# Sheet2.net
KiCad netlist of a schematic drawn in Altium Designer
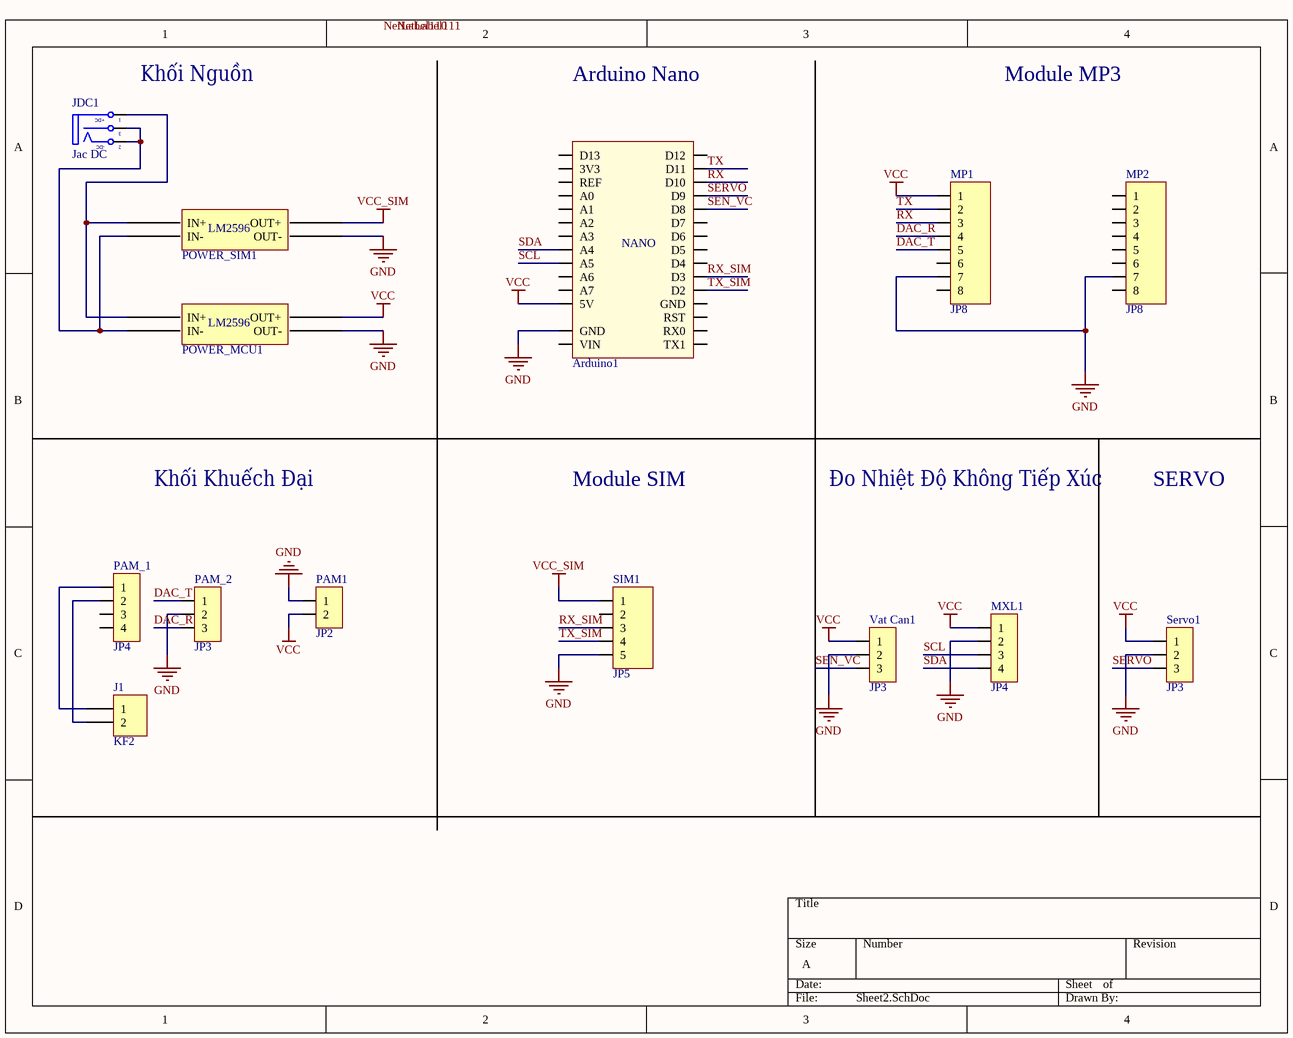
[diagram p0: Sheet2.SchDoc]

(export (version "E")
  (design (tool "Eeschema 10.0.6"))
  (components
    (comp (ref "Arduino1")
      (value "Arduino Nano")
      (footprint "Arduino Nano")
      (description "Arduino NANO")
      (libsource (lib "LIBRARY") (part "Arduino Nano"))
    )
    (comp (ref "J1")
      (value "KF2")
      (footprint "KF2-3.5")
      (fields
        (field (name "MANUFACTURER") "Würth Elektronik eiSos GmbH")
        (field (name "PARTNO") "691103110002")
        (field (name "CREATED BY") "Karrer Zheng")
      )
      (libsource (lib "LIBRARY") (part "KF2"))
    )
    (comp (ref "JDC1")
      (value "Jac DC")
      (footprint "DC0")
      (description "Jac DC input")
      (libsource (lib "LIBRARY") (part "DCIN"))
    )
    (comp (ref "MP1")
      (value "JP8")
      (footprint "JP8-C1C")
      (description "WR-PHD 2.54 mm Angled Socket Header")
      (fields
        (field (name "MANUFACTURER") "Würth Elektronik eiSos GmbH")
        (field (name "PARTNO") "613008143121")
        (field (name "CREATED BY") "Karrer Zheng")
      )
      (libsource (lib "LIBRARY") (part "JP8"))
    )
    (comp (ref "MP2")
      (value "JP8")
      (footprint "JP8-C1C")
      (description "WR-PHD 2.54 mm Angled Socket Header")
      (fields
        (field (name "MANUFACTURER") "Würth Elektronik eiSos GmbH")
        (field (name "PARTNO") "613008143121")
        (field (name "CREATED BY") "Karrer Zheng")
      )
      (libsource (lib "LIBRARY") (part "JP8"))
    )
    (comp (ref "MXL1")
      (value "JP4")
      (footprint "JP4-C1T")
      (description "WR-PHD 2.54 mm Angled Socket Header")
      (fields
        (field (name "MANUFACTURER") "Würth Elektronik eiSos GmbH")
        (field (name "PARTNO") "613004143121")
        (field (name "CREATED BY") "Karrer Zheng")
      )
      (libsource (lib "LIBRARY") (part "JP4"))
    )
    (comp (ref "PAM1")
      (value "JP2")
      (footprint "JP2-C1T")
      (description "WR-PHD 2.54 mm Angled Socket Header")
      (fields
        (field (name "MANUFACTURER") "Würth Elektronik eiSos GmbH")
        (field (name "PARTNO") "613002143121")
        (field (name "CREATED BY") "Karrer Zheng")
      )
      (libsource (lib "LIBRARY") (part "JP2"))
    )
    (comp (ref "PAM_1")
      (value "JP4")
      (footprint "JP4-C1T")
      (description "WR-PHD 2.54 mm Angled Socket Header")
      (fields
        (field (name "MANUFACTURER") "Würth Elektronik eiSos GmbH")
        (field (name "PARTNO") "613004143121")
        (field (name "CREATED BY") "Karrer Zheng")
      )
      (libsource (lib "LIBRARY") (part "JP4"))
    )
    (comp (ref "PAM_2")
      (value "JP3")
      (footprint "JP3-C1T")
      (description "WR-PHD 2.54 mm Angled Socket Header")
      (fields
        (field (name "MANUFACTURER") "Würth Elektronik eiSos GmbH")
        (field (name "PARTNO") "613003143121")
        (field (name "CREATED BY") "Karrer Zheng")
      )
      (libsource (lib "LIBRARY") (part "JP3"))
    )
    (comp (ref "POWER_MCU1")
      (value "BUCK_LM2596")
      (footprint "BUCK_LM2596")
      (libsource (lib "BUCK_LM2596_Sch") (part "BUCK_LM2596"))
    )
    (comp (ref "POWER_SIM1")
      (value "BUCK_LM2596")
      (footprint "BUCK_LM2596")
      (libsource (lib "BUCK_LM2596_Sch") (part "BUCK_LM2596"))
    )
    (comp (ref "Servo1")
      (value "JP3")
      (footprint "JP3-C1T")
      (description "WR-PHD 2.54 mm Angled Socket Header")
      (fields
        (field (name "MANUFACTURER") "Würth Elektronik eiSos GmbH")
        (field (name "PARTNO") "613003143121")
        (field (name "CREATED BY") "Karrer Zheng")
      )
      (libsource (lib "LIBRARY") (part "JP3"))
    )
    (comp (ref "SIM1")
      (value "JP5")
      (footprint "JP5-C1T")
      (description "WR-PHD 2.54 mm Angled Socket Header")
      (fields
        (field (name "MANUFACTURER") "Würth Elektronik eiSos GmbH")
        (field (name "PARTNO") "613005143121")
        (field (name "CREATED BY") "Karrer Zheng")
      )
      (libsource (lib "LIBRARY") (part "JP5"))
    )
    (comp (ref "Vat Can1")
      (value "JP3")
      (footprint "JP3-C1T")
      (description "WR-PHD 2.54 mm Angled Socket Header")
      (fields
        (field (name "MANUFACTURER") "Würth Elektronik eiSos GmbH")
        (field (name "PARTNO") "613003143121")
        (field (name "CREATED BY") "Karrer Zheng")
      )
      (libsource (lib "LIBRARY") (part "JP3"))
    )
  )
  (nets
    (net (code "1") (name "/DAC_R") (class "Default")
      (node (ref "MP1") (pin "4") (pinfunction "4_4") (pintype "passive"))
      (node (ref "PAM_2") (pin "3") (pinfunction "3_3") (pintype "passive"))
    )
    (net (code "2") (name "/DAC_T") (class "Default")
      (node (ref "MP1") (pin "5") (pinfunction "5_5") (pintype "passive"))
      (node (ref "PAM_2") (pin "1") (pinfunction "1_1") (pintype "passive"))
    )
    (net (code "5") (name "/RX") (class "Default")
      (node (ref "Arduino1") (pin "D10") (pinfunction "D10_D10") (pintype "passive"))
      (node (ref "MP1") (pin "3") (pinfunction "3_3") (pintype "passive"))
    )
    (net (code "6") (name "/RX_SIM") (class "Default")
      (node (ref "Arduino1") (pin "D3") (pinfunction "D3_D3") (pintype "passive"))
      (node (ref "SIM1") (pin "3") (pinfunction "3_3") (pintype "passive"))
    )
    (net (code "7") (name "/SCL") (class "Default")
      (node (ref "Arduino1") (pin "A5") (pinfunction "A5_A5") (pintype "passive"))
      (node (ref "MXL1") (pin "3") (pinfunction "3_3") (pintype "passive"))
    )
    (net (code "8") (name "/SDA") (class "Default")
      (node (ref "Arduino1") (pin "A4") (pinfunction "A4_A4") (pintype "passive"))
      (node (ref "MXL1") (pin "4") (pinfunction "4_4") (pintype "passive"))
    )
    (net (code "9") (name "/SEN_VC") (class "Default")
      (node (ref "Arduino1") (pin "D8") (pinfunction "D8_D8") (pintype "passive"))
      (node (ref "Vat Can1") (pin "3") (pinfunction "3_3") (pintype "passive"))
    )
    (net (code "10") (name "/SERVO") (class "Default")
      (node (ref "Arduino1") (pin "D9") (pinfunction "D9_D9") (pintype "passive"))
      (node (ref "Servo1") (pin "3") (pinfunction "3_3") (pintype "passive"))
    )
    (net (code "11") (name "/TX") (class "Default")
      (node (ref "Arduino1") (pin "D11") (pinfunction "D11_D11") (pintype "passive"))
      (node (ref "MP1") (pin "2") (pinfunction "2_2") (pintype "passive"))
    )
    (net (code "12") (name "/TX_SIM") (class "Default")
      (node (ref "Arduino1") (pin "D2") (pinfunction "D2_D2") (pintype "passive"))
      (node (ref "SIM1") (pin "4") (pinfunction "4_4") (pintype "passive"))
    )
    (net (code "13") (name "GND") (class "Default")
      (node (ref "Arduino1") (pin "GND") (pinfunction "GND_GND") (pintype "passive"))
      (node (ref "MP1") (pin "7") (pinfunction "7_7") (pintype "passive"))
      (node (ref "MP2") (pin "7") (pinfunction "7_7") (pintype "passive"))
      (node (ref "MXL1") (pin "2") (pinfunction "2_2") (pintype "passive"))
      (node (ref "PAM1") (pin "1") (pinfunction "1_1") (pintype "passive"))
      (node (ref "PAM_2") (pin "2") (pinfunction "2_2") (pintype "passive"))
      (node (ref "POWER_MCU1") (pin "3") (pinfunction "OUT-_3") (pintype "passive"))
      (node (ref "POWER_SIM1") (pin "3") (pinfunction "OUT-_3") (pintype "passive"))
      (node (ref "SIM1") (pin "5") (pinfunction "5_5") (pintype "passive"))
      (node (ref "Servo1") (pin "2") (pinfunction "2_2") (pintype "passive"))
      (node (ref "Vat Can1") (pin "2") (pinfunction "2_2") (pintype "passive"))
    )
    (net (code "14") (name "Net-(J1-Pad1)") (class "Default")
      (node (ref "J1") (pin "1") (pinfunction "1_1") (pintype "passive"))
      (node (ref "PAM_1") (pin "1") (pinfunction "1_1") (pintype "passive"))
    )
    (net (code "15") (name "Net-(J1-Pad2)") (class "Default")
      (node (ref "J1") (pin "2") (pinfunction "2_2") (pintype "passive"))
      (node (ref "PAM_1") (pin "2") (pinfunction "2_2") (pintype "passive"))
    )
    (net (code "16") (name "Net-(JDC1-S)") (class "Default")
      (node (ref "JDC1") (pin "2") (pinfunction "TN_2") (pintype "passive"))
      (node (ref "JDC1") (pin "3") (pinfunction "S_3") (pintype "power_in"))
      (node (ref "POWER_MCU1") (pin "2") (pinfunction "IN-_2") (pintype "passive"))
      (node (ref "POWER_SIM1") (pin "2") (pinfunction "IN-_2") (pintype "passive"))
    )
    (net (code "17") (name "Net-(JDC1-T)") (class "Default")
      (node (ref "JDC1") (pin "1") (pinfunction "T_1") (pintype "passive"))
      (node (ref "POWER_MCU1") (pin "1") (pinfunction "IN+_1") (pintype "passive"))
      (node (ref "POWER_SIM1") (pin "1") (pinfunction "IN+_1") (pintype "passive"))
    )
    (net (code "18") (name "VCC") (class "Default")
      (node (ref "Arduino1") (pin "5V") (pinfunction "5V_5V") (pintype "passive"))
      (node (ref "MP1") (pin "1") (pinfunction "1_1") (pintype "passive"))
      (node (ref "MXL1") (pin "1") (pinfunction "1_1") (pintype "passive"))
      (node (ref "PAM1") (pin "2") (pinfunction "2_2") (pintype "passive"))
      (node (ref "POWER_MCU1") (pin "4") (pinfunction "OUT+_4") (pintype "passive"))
      (node (ref "Servo1") (pin "1") (pinfunction "1_1") (pintype "passive"))
      (node (ref "Vat Can1") (pin "1") (pinfunction "1_1") (pintype "passive"))
    )
    (net (code "19") (name "VCC_SIM") (class "Default")
      (node (ref "POWER_SIM1") (pin "4") (pinfunction "OUT+_4") (pintype "passive"))
      (node (ref "SIM1") (pin "1") (pinfunction "1_1") (pintype "passive"))
    )
    (net (code "20") (name "unconnected-(Arduino1-Pad3V3)") (class "Default")
      (node (ref "Arduino1") (pin "3V3") (pinfunction "3V3_3V3") (pintype "passive"))
    )
    (net (code "21") (name "unconnected-(Arduino1-PadA0)") (class "Default")
      (node (ref "Arduino1") (pin "A0") (pinfunction "A0_A0") (pintype "passive"))
    )
    (net (code "22") (name "unconnected-(Arduino1-PadA1)") (class "Default")
      (node (ref "Arduino1") (pin "A1") (pinfunction "A1_A1") (pintype "passive"))
    )
    (net (code "23") (name "unconnected-(Arduino1-PadA2)") (class "Default")
      (node (ref "Arduino1") (pin "A2") (pinfunction "A2_A2") (pintype "passive"))
    )
    (net (code "24") (name "unconnected-(Arduino1-PadA3)") (class "Default")
      (node (ref "Arduino1") (pin "A3") (pinfunction "A3_A3") (pintype "passive"))
    )
    (net (code "25") (name "unconnected-(Arduino1-PadA6)") (class "Default")
      (node (ref "Arduino1") (pin "A6") (pinfunction "A6_A6") (pintype "passive"))
    )
    (net (code "26") (name "unconnected-(Arduino1-PadA7)") (class "Default")
      (node (ref "Arduino1") (pin "A7") (pinfunction "A7_A7") (pintype "passive"))
    )
    (net (code "27") (name "unconnected-(Arduino1-PadD4)") (class "Default")
      (node (ref "Arduino1") (pin "D4") (pinfunction "D4_D4") (pintype "passive"))
    )
    (net (code "28") (name "unconnected-(Arduino1-PadD5)") (class "Default")
      (node (ref "Arduino1") (pin "D5") (pinfunction "D5_D5") (pintype "passive"))
    )
    (net (code "29") (name "unconnected-(Arduino1-PadD6)") (class "Default")
      (node (ref "Arduino1") (pin "D6") (pinfunction "D6_D6") (pintype "passive"))
    )
    (net (code "30") (name "unconnected-(Arduino1-PadD7)") (class "Default")
      (node (ref "Arduino1") (pin "D7") (pinfunction "D7_D7") (pintype "passive"))
    )
    (net (code "31") (name "unconnected-(Arduino1-PadD12)") (class "Default")
      (node (ref "Arduino1") (pin "D12") (pinfunction "D12_D12") (pintype "passive"))
    )
    (net (code "32") (name "unconnected-(Arduino1-PadD13)") (class "Default")
      (node (ref "Arduino1") (pin "D13") (pinfunction "D13_D13") (pintype "passive"))
    )
    (net (code "33") (name "unconnected-(Arduino1-PadGND)") (class "Default")
      (node (ref "Arduino1") (pin "GND") (pinfunction "GND_GND") (pintype "passive"))
    )
    (net (code "34") (name "unconnected-(Arduino1-PadREF)") (class "Default")
      (node (ref "Arduino1") (pin "REF") (pinfunction "REF_REF") (pintype "passive"))
    )
    (net (code "35") (name "unconnected-(Arduino1-PadRST)") (class "Default")
      (node (ref "Arduino1") (pin "RST") (pinfunction "RST_RST") (pintype "passive"))
    )
    (net (code "36") (name "unconnected-(Arduino1-PadRST)_1") (class "Default")
      (node (ref "Arduino1") (pin "RST") (pinfunction "RST_RST") (pintype "passive"))
    )
    (net (code "37") (name "unconnected-(Arduino1-PadRX0)") (class "Default")
      (node (ref "Arduino1") (pin "RX0") (pinfunction "RX0_RX0") (pintype "passive"))
    )
    (net (code "38") (name "unconnected-(Arduino1-PadTX1)") (class "Default")
      (node (ref "Arduino1") (pin "TX1") (pinfunction "TX1_TX1") (pintype "passive"))
    )
    (net (code "39") (name "unconnected-(Arduino1-PadVIN)") (class "Default")
      (node (ref "Arduino1") (pin "VIN") (pinfunction "VIN_VIN") (pintype "passive"))
    )
    (net (code "40") (name "unconnected-(MP1-Pad6)") (class "Default")
      (node (ref "MP1") (pin "6") (pinfunction "6_6") (pintype "passive"))
    )
    (net (code "41") (name "unconnected-(MP1-Pad8)") (class "Default")
      (node (ref "MP1") (pin "8") (pinfunction "8_8") (pintype "passive"))
    )
    (net (code "42") (name "unconnected-(MP2-Pad1)") (class "Default")
      (node (ref "MP2") (pin "1") (pinfunction "1_1") (pintype "passive"))
    )
    (net (code "43") (name "unconnected-(MP2-Pad2)") (class "Default")
      (node (ref "MP2") (pin "2") (pinfunction "2_2") (pintype "passive"))
    )
    (net (code "44") (name "unconnected-(MP2-Pad3)") (class "Default")
      (node (ref "MP2") (pin "3") (pinfunction "3_3") (pintype "passive"))
    )
    (net (code "45") (name "unconnected-(MP2-Pad4)") (class "Default")
      (node (ref "MP2") (pin "4") (pinfunction "4_4") (pintype "passive"))
    )
    (net (code "46") (name "unconnected-(MP2-Pad5)") (class "Default")
      (node (ref "MP2") (pin "5") (pinfunction "5_5") (pintype "passive"))
    )
    (net (code "47") (name "unconnected-(MP2-Pad6)") (class "Default")
      (node (ref "MP2") (pin "6") (pinfunction "6_6") (pintype "passive"))
    )
    (net (code "48") (name "unconnected-(MP2-Pad8)") (class "Default")
      (node (ref "MP2") (pin "8") (pinfunction "8_8") (pintype "passive"))
    )
    (net (code "49") (name "unconnected-(PAM_1-Pad3)") (class "Default")
      (node (ref "PAM_1") (pin "3") (pinfunction "3_3") (pintype "passive"))
    )
    (net (code "50") (name "unconnected-(PAM_1-Pad4)") (class "Default")
      (node (ref "PAM_1") (pin "4") (pinfunction "4_4") (pintype "passive"))
    )
    (net (code "51") (name "unconnected-(SIM1-Pad2)") (class "Default")
      (node (ref "SIM1") (pin "2") (pinfunction "2_2") (pintype "passive"))
    )
  )
)
